# INTERNAL_REGULATORS.net
KiCad netlist of a schematic drawn in Altium Designer
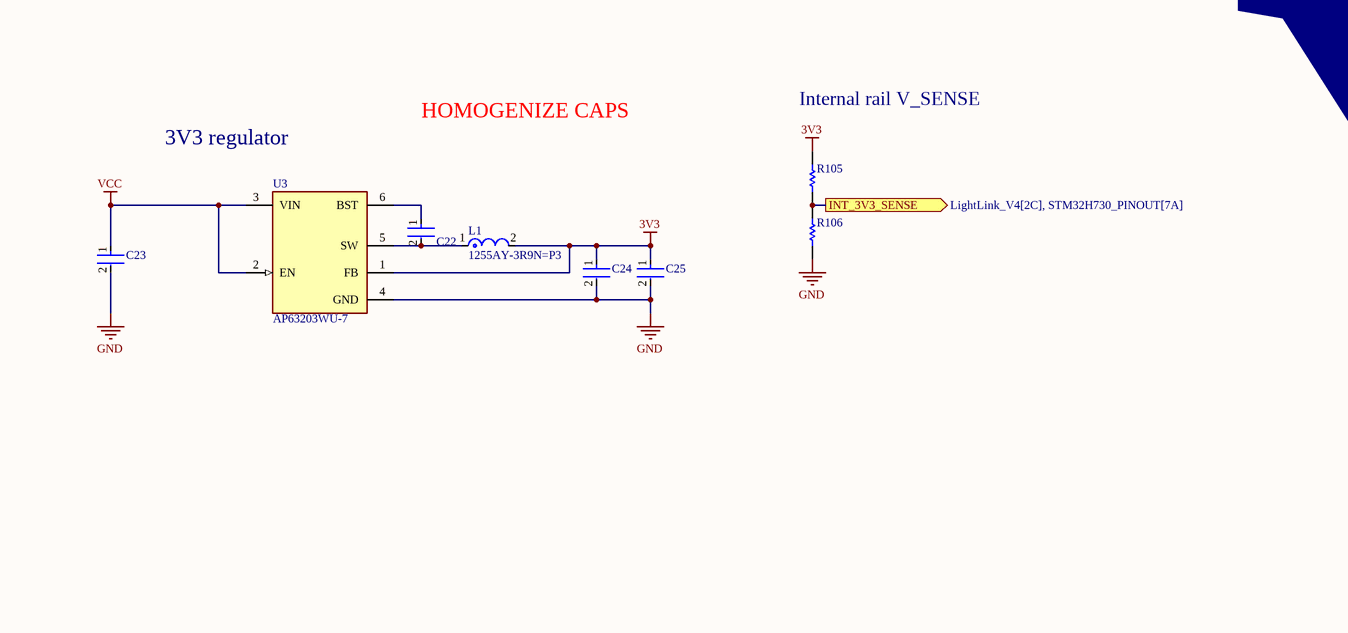
[diagram p0: INTERNAL_REGULATORS.SchDoc, top left]
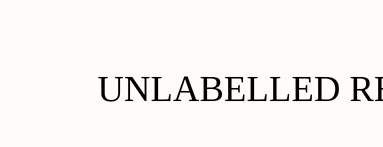
[diagram p1: INTERNAL_REGULATORS.SchDoc, bottom middle]

(export (version "E")
  (design (tool "Eeschema 10.0.6"))
  (components
    (comp (ref "C22")
      (value "C0402C104K8PACTU")
      (footprint "FP-C0402-BB-MFG")
      (description "CAP CER 0.1UF 10V X5R 0402")
      (fields (field (name "MANUFACTURER") "Kemet") (field (name "TOLERANCE") "0.1"))
      (libsource (lib "Altium Content Vault") (part "b4654b650e69147ec39a6b967a45e02"))
    )
    (comp (ref "C23")
      (value "GRM188R60J106ME47D")
      (footprint "FP-GRM188-0_1-e0_2_0_55-IPC_A")
      (description "Chip Multilayer Ceramic Capacitors for General Purpose, 0603, 10uF, X5R, 15%, 20%, 6.3V")
      (fields (field (name "VOLTAGE") "6.3V") (field (name "TOLERANCE") "20%"))
      (libsource (lib "Altium Content Vault") (part "02cd4be3c70576c341d710602a673aa"))
    )
    (comp (ref "C24")
      (value "GRM21BR61E226ME44L")
      (footprint "FP-GRM21B-0_2-e0_2_0_7-IPC_B")
      (description "Chip Multilayer Ceramic Capacitors for General Purpose, 0805, 22uF, X5R, 15%, 20%, 25V")
      (fields (field (name "TOLERANCE") "20%") (field (name "VOLTAGE") "25V"))
      (libsource (lib "Altium Content Vault") (part "b4654b650e69147ec39a6b967a45e02"))
    )
    (comp (ref "C25")
      (value "GRM21BR61E226ME44L")
      (footprint "FP-GRM21B-0_2-e0_2_0_7-IPC_B")
      (description "Chip Multilayer Ceramic Capacitors for General Purpose, 0805, 22uF, X5R, 15%, 20%, 25V")
      (fields (field (name "TOLERANCE") "20%") (field (name "VOLTAGE") "25V"))
      (libsource (lib "Altium Content Vault") (part "b4654b650e69147ec39a6b967a45e02"))
    )
    (comp (ref "L1")
      (value "1255AY-3R9N=P3")
      (footprint "FP-DG6045C-MFG")
      (description "Shielded Wirewound Inductor 3.9uH 30% 4200mA 0.0264Ω SMD")
      (fields (field (name "TOLERANCE") "30%"))
      (libsource (lib "Altium Content Vault") (part "4cc4b267dca4c8e51f7102f422741d8"))
    )
    (comp (ref "R105")
      (value "ERJ3EKF1002V")
      (footprint "RESC1609X55X30LL15T15")
      (description "Chip Resistor, 10 KOhm, +/- 1%, 0.1 W, -55 to 155 degC, 0603 (1608 Metric), RoHS, Tape and Reel")
      (fields (field (name "TOLERANCE") "1%") (field (name "MANUFACTURER") "Panasonic"))
      (libsource (lib "Altium Content Vault") (part "RES-2"))
    )
    (comp (ref "R106")
      (value "ERJ3EKF1002V")
      (footprint "RESC1609X55X30LL15T15")
      (description "Chip Resistor, 10 KOhm, +/- 1%, 0.1 W, -55 to 155 degC, 0603 (1608 Metric), RoHS, Tape and Reel")
      (fields (field (name "TOLERANCE") "1%") (field (name "MANUFACTURER") "Panasonic"))
      (libsource (lib "Altium Content Vault") (part "RES-2"))
    )
    (comp (ref "U3")
      (value "AP63203WU-7")
      (footprint "FP-TSOT26-MFG")
      (description "IC REG BUCK 3.3V 2A TSOT26")
      (fields
        (field (name "MANUFACTURER") "Diodes Inc.")
        (field (name "OCTOPART") "https://octopart.com/ap63203wu-7-diodes+inc.-98099550")
      )
      (libsource (lib "Altium Content Vault") (part "0e61c2974d7114b43f01ef96ae2e524"))
    )
  )
  (nets
    (net (code "1") (name "/INT_3V3_SENSE") (class "Default")
      (node (ref "R105") (pin "1") (pinfunction "1_1") (pintype "passive"))
      (node (ref "R106") (pin "2") (pinfunction "2_2") (pintype "passive"))
    )
    (net (code "2") (name "3V3") (class "Default")
      (node (ref "C24") (pin "1") (pinfunction "1_1") (pintype "passive"))
      (node (ref "C25") (pin "1") (pinfunction "1_1") (pintype "passive"))
      (node (ref "L1") (pin "2") (pinfunction "2_2") (pintype "passive"))
      (node (ref "R105") (pin "2") (pinfunction "2_2") (pintype "passive"))
      (node (ref "U3") (pin "1") (pinfunction "FB_1") (pintype "passive"))
    )
    (net (code "3") (name "GND") (class "Default")
      (node (ref "C23") (pin "2") (pinfunction "2_2") (pintype "passive"))
      (node (ref "C24") (pin "2") (pinfunction "2_2") (pintype "passive"))
      (node (ref "C25") (pin "2") (pinfunction "2_2") (pintype "passive"))
      (node (ref "R106") (pin "1") (pinfunction "1_1") (pintype "passive"))
      (node (ref "U3") (pin "4") (pinfunction "GND_4") (pintype "power_in"))
    )
    (net (code "4") (name "Net-(U3-BST)") (class "Default")
      (node (ref "C22") (pin "1") (pinfunction "1_1") (pintype "passive"))
      (node (ref "U3") (pin "6") (pinfunction "BST_6") (pintype "passive"))
    )
    (net (code "5") (name "Net-(U3-SW)") (class "Default")
      (node (ref "C22") (pin "2") (pinfunction "2_2") (pintype "passive"))
      (node (ref "L1") (pin "1") (pinfunction "1_1") (pintype "passive"))
      (node (ref "U3") (pin "5") (pinfunction "SW_5") (pintype "passive"))
    )
    (net (code "6") (name "VCC") (class "Default")
      (node (ref "C23") (pin "1") (pinfunction "1_1") (pintype "passive"))
      (node (ref "U3") (pin "2") (pinfunction "EN_2") (pintype "input"))
      (node (ref "U3") (pin "3") (pinfunction "VIN_3") (pintype "power_in"))
    )
  )
)
